# elektrosluch.net
KiCad netlist of a schematic drawn in EAGLE
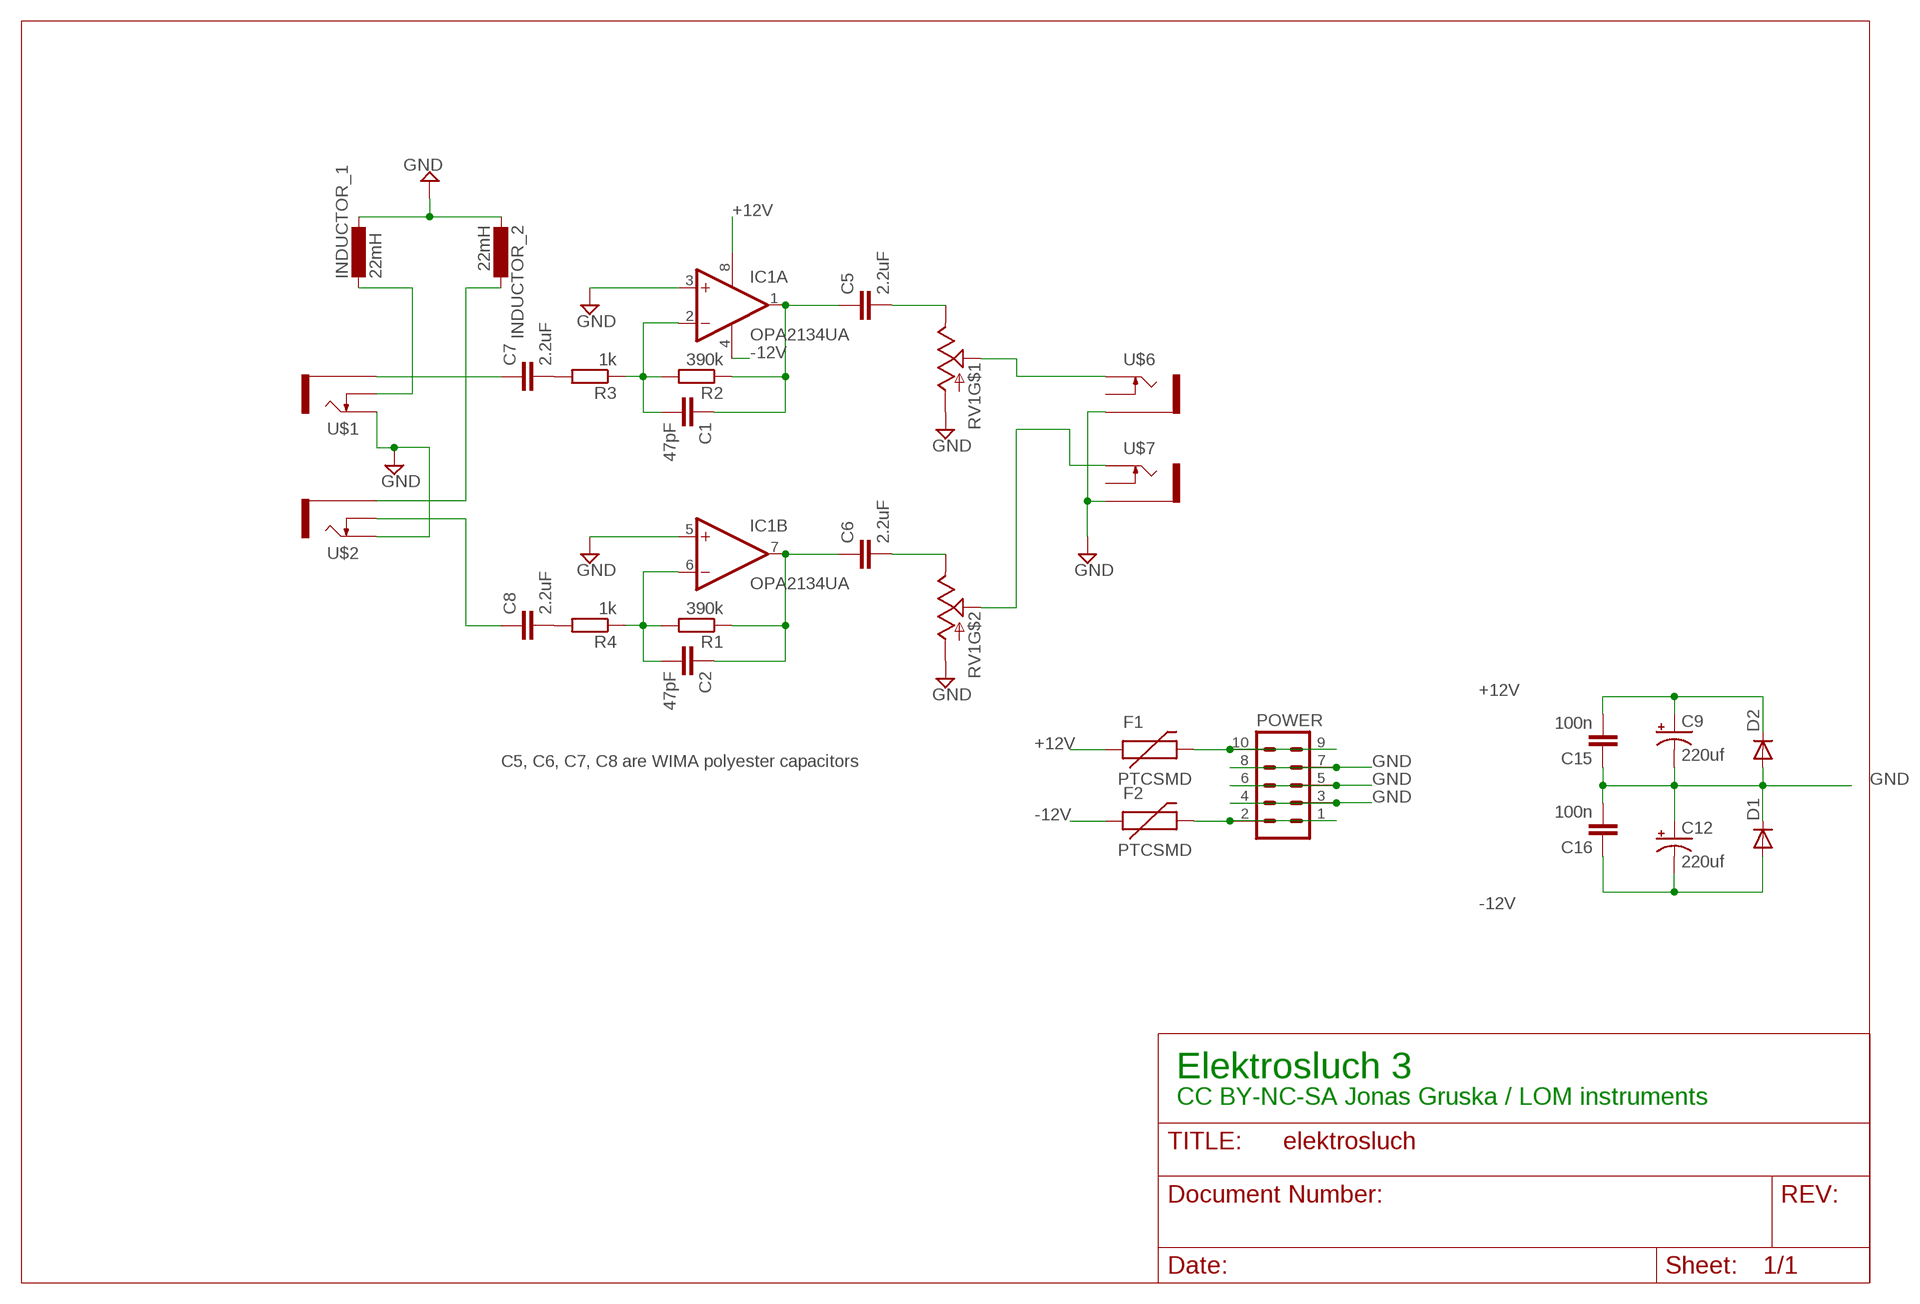
[diagram p0: schematic, sheet 1]

(export (version "E")
  (design (tool "Eeschema 10.0.6"))
  (components
    (comp (ref "C1")
      (value "47pF")
      (footprint "eagle-import:C0805")
      (libsource (lib "eagle-import") (part "rcl_C-EUC0805"))
    )
    (comp (ref "C2")
      (value "47pF")
      (footprint "eagle-import:C0805")
      (libsource (lib "eagle-import") (part "rcl_C-EUC0805"))
    )
    (comp (ref "C5")
      (value "2.2uF")
      (footprint "eagle-import:WIMA10UF")
      (libsource (lib "eagle-import") (part "WIMA10UF"))
    )
    (comp (ref "C6")
      (value "2.2uF")
      (footprint "eagle-import:WIMA10UF")
      (libsource (lib "eagle-import") (part "WIMA10UF"))
    )
    (comp (ref "C7")
      (value "2.2uF")
      (footprint "eagle-import:WIMA10UF")
      (libsource (lib "eagle-import") (part "WIMA10UF"))
    )
    (comp (ref "C8")
      (value "2.2uF")
      (footprint "eagle-import:WIMA10UF")
      (libsource (lib "eagle-import") (part "WIMA10UF"))
    )
    (comp (ref "C9")
      (value "220uf")
      (footprint "eagle-import:CPOL-RADIAL-10UF-25V")
      (libsource (lib "eagle-import") (part "CAP_POLPTH2"))
    )
    (comp (ref "C12")
      (value "220uf")
      (footprint "eagle-import:CPOL-RADIAL-10UF-25V")
      (libsource (lib "eagle-import") (part "CAP_POLPTH2"))
    )
    (comp (ref "C15")
      (value "100n")
      (footprint "eagle-import:R0805")
      (libsource (lib "eagle-import") (part "C-EU0805_CAP"))
    )
    (comp (ref "C16")
      (value "100n")
      (footprint "eagle-import:R0805")
      (libsource (lib "eagle-import") (part "C-EU0805_CAP"))
    )
    (comp (ref "D1")
      (value "DIODE-SOD123")
      (footprint "eagle-import:SOD123")
      (libsource (lib "eagle-import") (part "DIODE-SOD123"))
    )
    (comp (ref "D2")
      (value "DIODE-SOD123")
      (footprint "eagle-import:SOD123")
      (libsource (lib "eagle-import") (part "DIODE-SOD123"))
    )
    (comp (ref "F1")
      (value "PTCSMD")
      (footprint "eagle-import:PTC-1206")
      (libsource (lib "eagle-import") (part "PTCSMD"))
    )
    (comp (ref "F2")
      (value "PTCSMD")
      (footprint "eagle-import:PTC-1206")
      (libsource (lib "eagle-import") (part "PTCSMD"))
    )
    (comp (ref "IC1")
      (value "OPA2134UA")
      (footprint "eagle-import:SO08")
      (libsource (lib "eagle-import") (part "OPA2UA134"))
    )
    (comp (ref "INDUCTOR_1")
      (value "22mH")
      (footprint "eagle-import:COIL")
      (libsource (lib "eagle-import") (part "COIL"))
    )
    (comp (ref "INDUCTOR_2")
      (value "22mH")
      (footprint "eagle-import:COIL")
      (libsource (lib "eagle-import") (part "COIL"))
    )
    (comp (ref "POWER")
      (value "10_PIN_HEADER")
      (footprint "eagle-import:MA05-2")
      (libsource (lib "eagle-import") (part "10_PIN_HEADER"))
    )
    (comp (ref "R1")
      (value "390k")
      (footprint "eagle-import:R0805")
      (libsource (lib "eagle-import") (part "R-EU_R0805"))
    )
    (comp (ref "R2")
      (value "390k")
      (footprint "eagle-import:R0805")
      (libsource (lib "eagle-import") (part "R-EU_R0805"))
    )
    (comp (ref "R3")
      (value "1k")
      (footprint "eagle-import:R0805")
      (libsource (lib "eagle-import") (part "R-EU_R0805"))
    )
    (comp (ref "R4")
      (value "1k")
      (footprint "eagle-import:R0805")
      (libsource (lib "eagle-import") (part "R-EU_R0805"))
    )
    (comp (ref "RV1")
      (value "POT_DUAL")
      (footprint "eagle-import:POT_PANASONIC_DUAL_VERT_KIT")
      (libsource (lib "eagle-import") (part "POT_DUAL"))
    )
    (comp (ref "U$1")
      (value "THONKICONNNEW")
      (footprint "eagle-import:WQP-PJ301M-12_JACK")
      (libsource (lib "eagle-import") (part "THONKICONNNEW"))
    )
    (comp (ref "U$2")
      (value "THONKICONNNEW")
      (footprint "eagle-import:WQP-PJ301M-12_JACK")
      (libsource (lib "eagle-import") (part "THONKICONNNEW"))
    )
    (comp (ref "U$6")
      (value "THONKICONNNEW")
      (footprint "eagle-import:WQP-PJ301M-12_JACK")
      (libsource (lib "eagle-import") (part "THONKICONNNEW"))
    )
    (comp (ref "U$7")
      (value "THONKICONNNEW")
      (footprint "eagle-import:WQP-PJ301M-12_JACK")
      (libsource (lib "eagle-import") (part "THONKICONNNEW"))
    )
  )
  (nets
    (net (code "1") (name "/+12V") (class "Default")
      (node (ref "C15") (pin "2") (pinfunction "2_2") (pintype "passive"))
      (node (ref "C9") (pin "1") (pinfunction "+_1") (pintype "passive"))
      (node (ref "D2") (pin "C") (pinfunction "C_C") (pintype "passive"))
      (node (ref "F1") (pin "1") (pinfunction "1_1") (pintype "bidirectional"))
      (node (ref "IC1") (pin "8") (pinfunction "V+_8") (pintype "power_in"))
    )
    (net (code "2") (name "/-12V") (class "Default")
      (node (ref "C12") (pin "2") (pinfunction "-_2") (pintype "passive"))
      (node (ref "C16") (pin "1") (pinfunction "1_1") (pintype "passive"))
      (node (ref "D1") (pin "A") (pinfunction "A_A") (pintype "passive"))
      (node (ref "F2") (pin "1") (pinfunction "1_1") (pintype "bidirectional"))
      (node (ref "IC1") (pin "4") (pinfunction "V-_4") (pintype "power_in"))
    )
    (net (code "3") (name "GND") (class "Default")
      (node (ref "C12") (pin "1") (pinfunction "+_1") (pintype "passive"))
      (node (ref "C15") (pin "1") (pinfunction "1_1") (pintype "passive"))
      (node (ref "C16") (pin "2") (pinfunction "2_2") (pintype "passive"))
      (node (ref "C9") (pin "2") (pinfunction "-_2") (pintype "passive"))
      (node (ref "D1") (pin "C") (pinfunction "C_C") (pintype "passive"))
      (node (ref "D2") (pin "A") (pinfunction "A_A") (pintype "passive"))
      (node (ref "IC1") (pin "3") (pinfunction "+IN_3") (pintype "input"))
      (node (ref "IC1") (pin "5") (pinfunction "+IN_5") (pintype "input"))
      (node (ref "INDUCTOR_1") (pin "P$1") (pinfunction "1_P$1") (pintype "passive"))
      (node (ref "INDUCTOR_2") (pin "P$2") (pinfunction "2_P$2") (pintype "passive"))
      (node (ref "POWER") (pin "3") (pinfunction "3_3") (pintype "passive"))
      (node (ref "POWER") (pin "4") (pinfunction "4_4") (pintype "passive"))
      (node (ref "POWER") (pin "5") (pinfunction "5_5") (pintype "passive"))
      (node (ref "POWER") (pin "6") (pinfunction "6_6") (pintype "passive"))
      (node (ref "POWER") (pin "7") (pinfunction "7_7") (pintype "passive"))
      (node (ref "POWER") (pin "8") (pinfunction "8_8") (pintype "passive"))
      (node (ref "RV1") (pin "A3") (pinfunction "A_A3") (pintype "passive"))
      (node (ref "RV1") (pin "B3") (pinfunction "A_B3") (pintype "passive"))
      (node (ref "U$1") (pin "P$1_TIP") (pinfunction "TIP_P$1_TIP") (pintype "passive"))
      (node (ref "U$2") (pin "P$1_TIP") (pinfunction "TIP_P$1_TIP") (pintype "passive"))
      (node (ref "U$6") (pin "P$3_SLEEVE") (pinfunction "SLEEVE_P$3_SLEEVE") (pintype "passive"))
      (node (ref "U$7") (pin "P$3_SLEEVE") (pinfunction "SLEEVE_P$3_SLEEVE") (pintype "passive"))
    )
    (net (code "4") (name "Net-(C5-1)") (class "Default")
      (node (ref "C1") (pin "1") (pinfunction "1_1") (pintype "passive"))
      (node (ref "C5") (pin "P$1") (pinfunction "1_P$1") (pintype "passive"))
      (node (ref "IC1") (pin "1") (pinfunction "OUT_1") (pintype "output"))
      (node (ref "R2") (pin "1") (pinfunction "1_1") (pintype "passive"))
    )
    (net (code "5") (name "Net-(C5-2)") (class "Default")
      (node (ref "C5") (pin "P$2") (pinfunction "2_P$2") (pintype "passive"))
      (node (ref "RV1") (pin "A1") (pinfunction "E_A1") (pintype "passive"))
    )
    (net (code "6") (name "Net-(C6-1)") (class "Default")
      (node (ref "C2") (pin "1") (pinfunction "1_1") (pintype "passive"))
      (node (ref "C6") (pin "P$1") (pinfunction "1_P$1") (pintype "passive"))
      (node (ref "IC1") (pin "7") (pinfunction "OUT_7") (pintype "output"))
      (node (ref "R1") (pin "1") (pinfunction "1_1") (pintype "passive"))
    )
    (net (code "7") (name "Net-(C6-2)") (class "Default")
      (node (ref "C6") (pin "P$2") (pinfunction "2_P$2") (pintype "passive"))
      (node (ref "RV1") (pin "B1") (pinfunction "E_B1") (pintype "passive"))
    )
    (net (code "8") (name "Net-(C7-1)") (class "Default")
      (node (ref "C7") (pin "P$1") (pinfunction "1_P$1") (pintype "passive"))
      (node (ref "U$1") (pin "P$3_SLEEVE") (pinfunction "SLEEVE_P$3_SLEEVE") (pintype "passive"))
    )
    (net (code "9") (name "Net-(C7-2)") (class "Default")
      (node (ref "C7") (pin "P$2") (pinfunction "2_P$2") (pintype "passive"))
      (node (ref "R3") (pin "2") (pinfunction "2_2") (pintype "passive"))
    )
    (net (code "10") (name "Net-(C8-1)") (class "Default")
      (node (ref "C8") (pin "P$1") (pinfunction "1_P$1") (pintype "passive"))
      (node (ref "U$2") (pin "P$2_SWITCH") (pinfunction "SWITCH_P$2_SWITCH") (pintype "passive"))
    )
    (net (code "11") (name "Net-(C8-2)") (class "Default")
      (node (ref "C8") (pin "P$2") (pinfunction "2_P$2") (pintype "passive"))
      (node (ref "R4") (pin "2") (pinfunction "2_2") (pintype "passive"))
    )
    (net (code "12") (name "Net-(F1-Pad2)") (class "Default")
      (node (ref "F1") (pin "2") (pinfunction "2_2") (pintype "bidirectional"))
      (node (ref "POWER") (pin "10") (pinfunction "10_10") (pintype "passive"))
      (node (ref "POWER") (pin "9") (pinfunction "9_9") (pintype "passive"))
    )
    (net (code "13") (name "Net-(F2-Pad2)") (class "Default")
      (node (ref "F2") (pin "2") (pinfunction "2_2") (pintype "bidirectional"))
      (node (ref "POWER") (pin "1") (pinfunction "1_1") (pintype "passive"))
      (node (ref "POWER") (pin "2") (pinfunction "2_2") (pintype "passive"))
    )
    (net (code "14") (name "Net-(IC1A--IN)") (class "Default")
      (node (ref "C1") (pin "2") (pinfunction "2_2") (pintype "passive"))
      (node (ref "IC1") (pin "2") (pinfunction "-IN_2") (pintype "input"))
      (node (ref "R2") (pin "2") (pinfunction "2_2") (pintype "passive"))
      (node (ref "R3") (pin "1") (pinfunction "1_1") (pintype "passive"))
    )
    (net (code "15") (name "Net-(IC1B--IN)") (class "Default")
      (node (ref "C2") (pin "2") (pinfunction "2_2") (pintype "passive"))
      (node (ref "IC1") (pin "6") (pinfunction "-IN_6") (pintype "input"))
      (node (ref "R1") (pin "2") (pinfunction "2_2") (pintype "passive"))
      (node (ref "R4") (pin "1") (pinfunction "1_1") (pintype "passive"))
    )
    (net (code "16") (name "Net-(INDUCTOR_1-2)") (class "Default")
      (node (ref "INDUCTOR_1") (pin "P$2") (pinfunction "2_P$2") (pintype "passive"))
      (node (ref "U$1") (pin "P$2_SWITCH") (pinfunction "SWITCH_P$2_SWITCH") (pintype "passive"))
    )
    (net (code "17") (name "Net-(INDUCTOR_2-1)") (class "Default")
      (node (ref "INDUCTOR_2") (pin "P$1") (pinfunction "1_P$1") (pintype "passive"))
      (node (ref "U$2") (pin "P$3_SLEEVE") (pinfunction "SLEEVE_P$3_SLEEVE") (pintype "passive"))
    )
    (net (code "18") (name "Net-(RV1A-S)") (class "Default")
      (node (ref "RV1") (pin "A2") (pinfunction "S_A2") (pintype "passive"))
      (node (ref "U$6") (pin "P$1_TIP") (pinfunction "TIP_P$1_TIP") (pintype "passive"))
    )
    (net (code "19") (name "Net-(RV1B-S)") (class "Default")
      (node (ref "RV1") (pin "B2") (pinfunction "S_B2") (pintype "passive"))
      (node (ref "U$7") (pin "P$1_TIP") (pinfunction "TIP_P$1_TIP") (pintype "passive"))
    )
    (net (code "20") (name "unconnected-(U$6-SWITCH-PadP$2_SWITCH)") (class "Default")
      (node (ref "U$6") (pin "P$2_SWITCH") (pinfunction "SWITCH_P$2_SWITCH") (pintype "passive"))
    )
    (net (code "21") (name "unconnected-(U$7-SWITCH-PadP$2_SWITCH)") (class "Default")
      (node (ref "U$7") (pin "P$2_SWITCH") (pinfunction "SWITCH_P$2_SWITCH") (pintype "passive"))
    )
  )
)
